# Infinity_Mirror_b_unbuilt.net
KiCad netlist of a schematic drawn in EAGLE
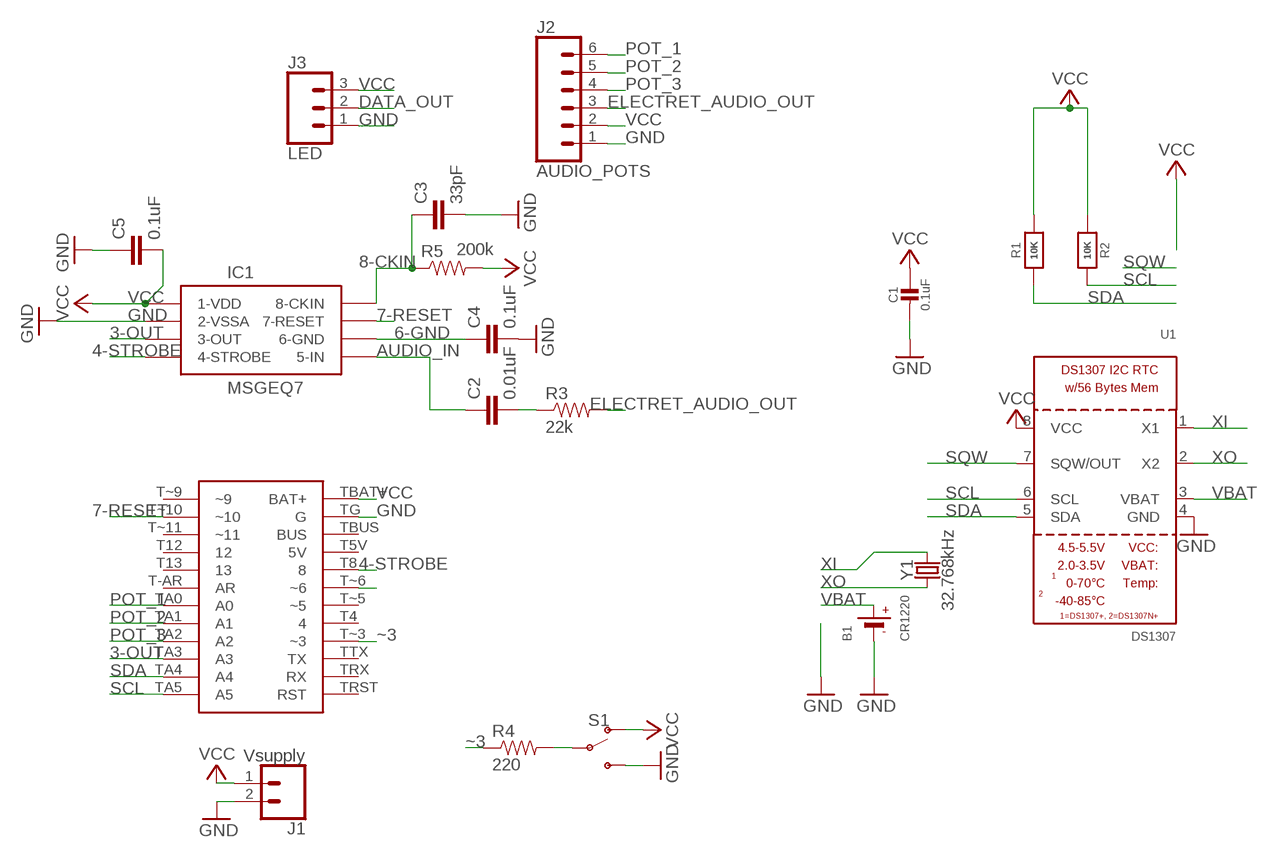
[diagram p0: schematic, sheet 1]

(export (version "E")
  (design (tool "Eeschema 10.0.6"))
  (components
    (comp (ref "B1")
      (value "CR1220")
      (footprint "eagle-import:CR1220")
      (libsource (lib "eagle-import") (part "BATTERYCR1220_SMT"))
    )
    (comp (ref "C1")
      (value "0.1uF")
      (footprint "eagle-import:0805-NO")
      (libsource (lib "eagle-import") (part "CAP_CERAMIC0805-NOOUTLINE"))
    )
    (comp (ref "C2")
      (value "0.01uF")
      (footprint "eagle-import:SPARKFUN-CAPACITORS_0805")
      (libsource (lib "eagle-import") (part "SPARKFUN-CAPACITORS_CAP0805"))
    )
    (comp (ref "C3")
      (value "33pF")
      (footprint "eagle-import:0805")
      (libsource (lib "eagle-import") (part "0.33UF/330NF-0805-50V-10%"))
    )
    (comp (ref "C4")
      (value "0.1uF")
      (footprint "eagle-import:SPARKFUN-CAPACITORS_0805")
      (libsource (lib "eagle-import") (part "SPARKFUN-CAPACITORS_CAP0805"))
    )
    (comp (ref "C5")
      (value "0.1uF")
      (footprint "eagle-import:SPARKFUN-CAPACITORS_0805")
      (libsource (lib "eagle-import") (part "SPARKFUN-CAPACITORS_CAP0805"))
    )
    (comp (ref "IC1")
      (value "MSGEQ7P")
      (footprint "eagle-import:DIP08")
      (libsource (lib "eagle-import") (part "MSGEQ7DIL"))
    )
    (comp (ref "J1")
      (value "Vsupply")
      (footprint "eagle-import:SPARKFUN-CONNECTORS_1X02_LOCK")
      (libsource (lib "eagle-import") (part "SPARKFUN-CONNECTORS_CONN_02LOCK"))
    )
    (comp (ref "J2")
      (value "AUDIO_POTS")
      (footprint "eagle-import:1X06")
      (libsource (lib "eagle-import") (part "CONN_06SILK_FEMALE_PTH"))
    )
    (comp (ref "J3")
      (value "LED")
      (footprint "eagle-import:1X03")
      (libsource (lib "eagle-import") (part "CONN_03"))
    )
    (comp (ref "R1")
      (value "10K")
      (footprint "eagle-import:0805-NO")
      (libsource (lib "eagle-import") (part "RESISTOR0805_NOOUTLINE"))
    )
    (comp (ref "R2")
      (value "10K")
      (footprint "eagle-import:0805-NO")
      (libsource (lib "eagle-import") (part "RESISTOR0805_NOOUTLINE"))
    )
    (comp (ref "R3")
      (value "22k")
      (footprint "eagle-import:SPARKFUN-PASSIVES_0805")
      (libsource (lib "eagle-import") (part "SPARKFUN-PASSIVES_RESISTOR0805-RES"))
    )
    (comp (ref "R4")
      (value "220")
      (footprint "eagle-import:SPARKFUN-PASSIVES_0805")
      (libsource (lib "eagle-import") (part "SPARKFUN-PASSIVES_RESISTOR0805-RES"))
    )
    (comp (ref "R5")
      (value "200k")
      (footprint "eagle-import:SPARKFUN-PASSIVES_0805")
      (libsource (lib "eagle-import") (part "SPARKFUN-PASSIVES_RESISTOR0805-RES"))
    )
    (comp (ref "S1")
      (value "SWITCH-SPDT-PTH-11.6X4.0MM-LOCK")
      (footprint "eagle-import:SWITCH_SPDT_PTH_11.6X4.0MM_LOCK")
      (libsource (lib "eagle-import") (part "SWITCH-SPDT-PTH-11.6X4.0MM-LOCK"))
    )
    (comp (ref "U$1")
      (value "ADAFRUIT_PRO_TRINKET_NO-DIMENSION")
      (footprint "eagle-import:ARDUINO_PRO_TRINKET_5V_NO-DIMENSION")
      (libsource (lib "eagle-import") (part "ADAFRUIT_PRO_TRINKET_NO-DIMENSION"))
    )
    (comp (ref "U1")
      (value "DS1307")
      (footprint "eagle-import:SOIC8_150MIL")
      (libsource (lib "eagle-import") (part "RTC_DS1307"))
    )
    (comp (ref "Y1")
      (value "32.768kHz")
      (footprint "eagle-import:CRYSTAL-PTH-2X6-CYL")
      (libsource (lib "eagle-import") (part "CRYSTAL-32.768KHZPTH-2X6"))
    )
  )
  (nets
    (net (code "1") (name "/3-OUT") (class "Default")
      (node (ref "IC1") (pin "3") (pinfunction "3-OUT_3") (pintype "input"))
      (node (ref "U$1") (pin "TA3") (pinfunction "A3_TA3") (pintype "bidirectional"))
    )
    (net (code "2") (name "/4-STROBE") (class "Default")
      (node (ref "IC1") (pin "4") (pinfunction "4-STROBE_4") (pintype "input"))
      (node (ref "U$1") (pin "T8") (pinfunction "8_T8") (pintype "bidirectional"))
    )
    (net (code "3") (name "/6-GND") (class "Default")
      (node (ref "C4") (pin "1") (pinfunction "1_1") (pintype "passive"))
      (node (ref "IC1") (pin "6") (pinfunction "6-GND_6") (pintype "bidirectional"))
    )
    (net (code "4") (name "/7-RESET") (class "Default")
      (node (ref "IC1") (pin "7") (pinfunction "7-RESET_7") (pintype "bidirectional"))
      (node (ref "U$1") (pin "T~10") (pinfunction "~{10}_T~10") (pintype "bidirectional"))
    )
    (net (code "5") (name "/8-CKIN") (class "Default")
      (node (ref "C3") (pin "1") (pinfunction "1_1") (pintype "passive"))
      (node (ref "IC1") (pin "8") (pinfunction "8-CKIN_8") (pintype "bidirectional"))
      (node (ref "R5") (pin "1") (pinfunction "1_1") (pintype "passive"))
    )
    (net (code "6") (name "/AUDIO_IN") (class "Default")
      (node (ref "C2") (pin "1") (pinfunction "1_1") (pintype "passive"))
      (node (ref "IC1") (pin "5") (pinfunction "5-IN_5") (pintype "bidirectional"))
    )
    (net (code "7") (name "/DATA_OUT") (class "Default")
      (node (ref "J3") (pin "2") (pinfunction "2_2") (pintype "passive"))
      (node (ref "U$1") (pin "T~6") (pinfunction "~{6}_T~6") (pintype "bidirectional"))
    )
    (net (code "8") (name "/ELECTRET_AUDIO_OUT") (class "Default")
      (node (ref "J2") (pin "3") (pinfunction "3_3") (pintype "passive"))
      (node (ref "R3") (pin "2") (pinfunction "2_2") (pintype "passive"))
    )
    (net (code "9") (name "/POT_1") (class "Default")
      (node (ref "J2") (pin "6") (pinfunction "6_6") (pintype "passive"))
      (node (ref "U$1") (pin "TA0") (pinfunction "A0_TA0") (pintype "bidirectional"))
    )
    (net (code "10") (name "/POT_2") (class "Default")
      (node (ref "J2") (pin "5") (pinfunction "5_5") (pintype "passive"))
      (node (ref "U$1") (pin "TA1") (pinfunction "A1_TA1") (pintype "bidirectional"))
    )
    (net (code "11") (name "/POT_3") (class "Default")
      (node (ref "J2") (pin "4") (pinfunction "4_4") (pintype "passive"))
      (node (ref "U$1") (pin "TA2") (pinfunction "A2_TA2") (pintype "bidirectional"))
    )
    (net (code "12") (name "/SCL") (class "Default")
      (node (ref "R2") (pin "2") (pinfunction "2_2") (pintype "passive"))
      (node (ref "U$1") (pin "TA5") (pinfunction "A5_TA5") (pintype "bidirectional"))
      (node (ref "U1") (pin "6") (pinfunction "SCL_6") (pintype "bidirectional"))
    )
    (net (code "13") (name "/SDA") (class "Default")
      (node (ref "R1") (pin "1") (pinfunction "1_1") (pintype "passive"))
      (node (ref "U$1") (pin "TA4") (pinfunction "A4_TA4") (pintype "bidirectional"))
      (node (ref "U1") (pin "5") (pinfunction "SDA_5") (pintype "bidirectional"))
    )
    (net (code "14") (name "/SQW") (class "Default")
      (node (ref "U1") (pin "7") (pinfunction "SQW/OUT_7") (pintype "bidirectional"))
    )
    (net (code "15") (name "/VBAT") (class "Default")
      (node (ref "B1") (pin "+$1") (pinfunction "+_+$1") (pintype "passive"))
      (node (ref "U1") (pin "3") (pinfunction "VBAT_3") (pintype "bidirectional"))
    )
    (net (code "16") (name "/XI") (class "Default")
      (node (ref "U1") (pin "1") (pinfunction "X1_1") (pintype "bidirectional"))
      (node (ref "Y1") (pin "2") (pinfunction "2_2") (pintype "passive"))
    )
    (net (code "17") (name "/XO") (class "Default")
      (node (ref "U1") (pin "2") (pinfunction "X2_2") (pintype "bidirectional"))
      (node (ref "Y1") (pin "1") (pinfunction "1_1") (pintype "passive"))
    )
    (net (code "18") (name "/~{3}") (class "Default")
      (node (ref "R4") (pin "1") (pinfunction "1_1") (pintype "passive"))
      (node (ref "U$1") (pin "T~3") (pinfunction "~{3}_T~3") (pintype "bidirectional"))
    )
    (net (code "19") (name "GND") (class "Default")
      (node (ref "B1") (pin "-") (pinfunction "-_-") (pintype "passive"))
      (node (ref "C1") (pin "2") (pinfunction "2_2") (pintype "passive"))
      (node (ref "C3") (pin "2") (pinfunction "2_2") (pintype "passive"))
      (node (ref "C4") (pin "2") (pinfunction "2_2") (pintype "passive"))
      (node (ref "C5") (pin "1") (pinfunction "1_1") (pintype "passive"))
      (node (ref "IC1") (pin "2") (pinfunction "2-VSSA_2") (pintype "input"))
      (node (ref "J1") (pin "2") (pinfunction "2_2") (pintype "passive"))
      (node (ref "J2") (pin "1") (pinfunction "1_1") (pintype "passive"))
      (node (ref "J3") (pin "1") (pinfunction "1_1") (pintype "passive"))
      (node (ref "S1") (pin "3") (pinfunction "S_3") (pintype "passive"))
      (node (ref "U$1") (pin "TG") (pinfunction "G_TG") (pintype "bidirectional"))
      (node (ref "U1") (pin "4") (pinfunction "GND_4") (pintype "bidirectional"))
    )
    (net (code "20") (name "Net-(C2-Pad2)") (class "Default")
      (node (ref "C2") (pin "2") (pinfunction "2_2") (pintype "passive"))
      (node (ref "R3") (pin "1") (pinfunction "1_1") (pintype "passive"))
    )
    (net (code "21") (name "Net-(S1-P)") (class "Default")
      (node (ref "R4") (pin "2") (pinfunction "2_2") (pintype "passive"))
      (node (ref "S1") (pin "2") (pinfunction "P_2") (pintype "passive"))
    )
    (net (code "22") (name "VCC") (class "Default")
      (node (ref "C1") (pin "1") (pinfunction "1_1") (pintype "passive"))
      (node (ref "C5") (pin "2") (pinfunction "2_2") (pintype "passive"))
      (node (ref "IC1") (pin "1") (pinfunction "1-VDD_1") (pintype "input"))
      (node (ref "J1") (pin "1") (pinfunction "1_1") (pintype "passive"))
      (node (ref "J2") (pin "2") (pinfunction "2_2") (pintype "passive"))
      (node (ref "J3") (pin "3") (pinfunction "3_3") (pintype "passive"))
      (node (ref "R1") (pin "2") (pinfunction "2_2") (pintype "passive"))
      (node (ref "R2") (pin "1") (pinfunction "1_1") (pintype "passive"))
      (node (ref "R5") (pin "2") (pinfunction "2_2") (pintype "passive"))
      (node (ref "S1") (pin "1") (pinfunction "O_1") (pintype "passive"))
      (node (ref "U$1") (pin "TBAT+") (pinfunction "BAT+_TBAT+") (pintype "bidirectional"))
      (node (ref "U1") (pin "8") (pinfunction "VCC_8") (pintype "bidirectional"))
    )
    (net (code "23") (name "unconnected-(U$1-4-PadT4)") (class "Default")
      (node (ref "U$1") (pin "T4") (pinfunction "4_T4") (pintype "bidirectional"))
    )
    (net (code "24") (name "unconnected-(U$1-5V-PadT5V)") (class "Default")
      (node (ref "U$1") (pin "T5V") (pinfunction "5V_T5V") (pintype "bidirectional"))
    )
    (net (code "25") (name "unconnected-(U$1-12-PadT12)") (class "Default")
      (node (ref "U$1") (pin "T12") (pinfunction "12_T12") (pintype "bidirectional"))
    )
    (net (code "26") (name "unconnected-(U$1-13-PadT13)") (class "Default")
      (node (ref "U$1") (pin "T13") (pinfunction "13_T13") (pintype "bidirectional"))
    )
    (net (code "27") (name "unconnected-(U$1-AR-PadT-AR)") (class "Default")
      (node (ref "U$1") (pin "T-AR") (pinfunction "AR_T-AR") (pintype "bidirectional"))
    )
    (net (code "28") (name "unconnected-(U$1-BUS-PadTBUS)") (class "Default")
      (node (ref "U$1") (pin "TBUS") (pinfunction "BUS_TBUS") (pintype "bidirectional"))
    )
    (net (code "29") (name "unconnected-(U$1-RST-PadTRST)") (class "Default")
      (node (ref "U$1") (pin "TRST") (pinfunction "RST_TRST") (pintype "bidirectional"))
    )
    (net (code "30") (name "unconnected-(U$1-RX-PadTRX)") (class "Default")
      (node (ref "U$1") (pin "TRX") (pinfunction "RX_TRX") (pintype "bidirectional"))
    )
    (net (code "31") (name "unconnected-(U$1-TX-PadTTX)") (class "Default")
      (node (ref "U$1") (pin "TTX") (pinfunction "TX_TTX") (pintype "bidirectional"))
    )
    (net (code "32") (name "unconnected-(U$1-~{5}-PadT~5)") (class "Default")
      (node (ref "U$1") (pin "T~5") (pinfunction "~{5}_T~5") (pintype "bidirectional"))
    )
    (net (code "33") (name "unconnected-(U$1-~{9}-PadT~9)") (class "Default")
      (node (ref "U$1") (pin "T~9") (pinfunction "~{9}_T~9") (pintype "bidirectional"))
    )
    (net (code "34") (name "unconnected-(U$1-~{11}-PadT~11)") (class "Default")
      (node (ref "U$1") (pin "T~11") (pinfunction "~{11}_T~11") (pintype "bidirectional"))
    )
  )
)
